# VGA.net
KiCad netlist of a schematic drawn in Altium Designer
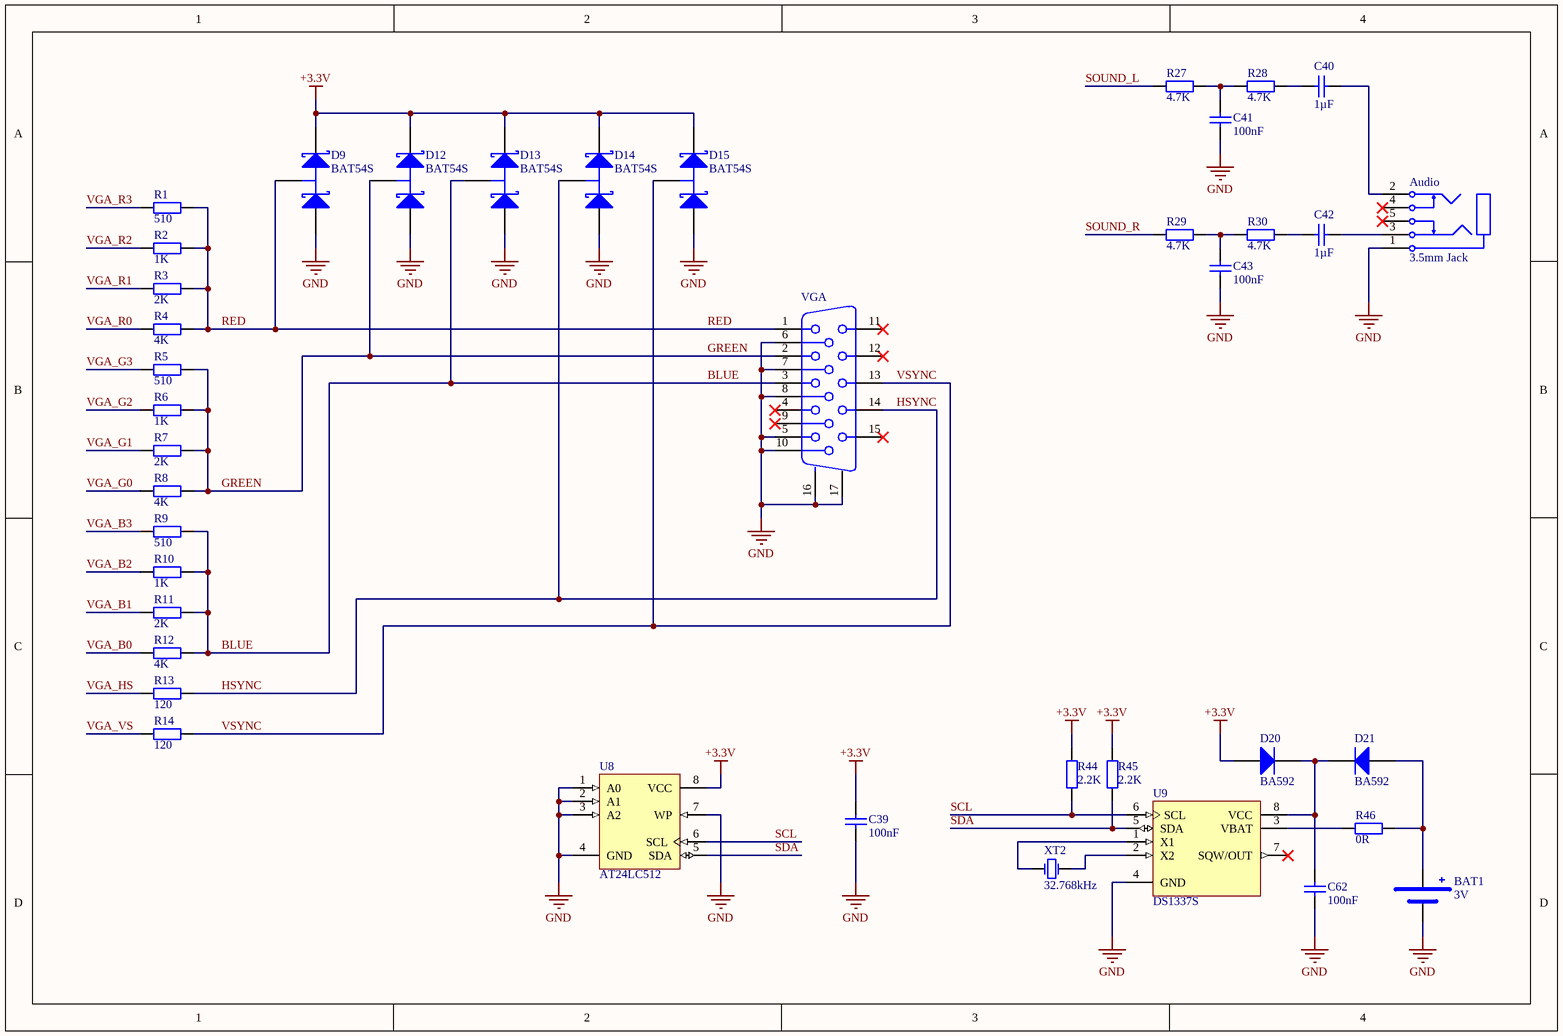
[diagram p0: VGA.SchDoc]

(export (version "E")
  (design (tool "Eeschema 10.0.6"))
  (components
    (comp (ref "Audio")
      (value "3.5mm Jack")
      (footprint "SJ1-353XNG")
      (libsource (lib "eon_lib") (part "Phono Jack"))
    )
    (comp (ref "BAT1")
      (value "3V")
      (footprint "CR2032 HOLDER - Vertical")
      (libsource (lib "eon_lib") (part "CR2032 Battery"))
    )
    (comp (ref "C39")
      (value "100nF")
      (footprint "RESC2012N")
      (description "Capacitor")
      (fields (field (name "PUBLISHER") "Altium Limited"))
      (libsource (lib "eon_lib") (part "Capacitor"))
    )
    (comp (ref "C40")
      (value "1µF")
      (footprint "6-0805_n")
      (description "Capacitor")
      (fields (field (name "Comment") "Cap") (field (name "PUBLISHER") "Altium Limited"))
      (libsource (lib "Miscellaneous Devices") (part "Cap"))
    )
    (comp (ref "C41")
      (value "100nF")
      (footprint "6-0805_n")
      (description "Capacitor")
      (fields (field (name "Comment") "Cap") (field (name "PUBLISHER") "Altium Limited"))
      (libsource (lib "Miscellaneous Devices") (part "Cap"))
    )
    (comp (ref "C42")
      (value "1µF")
      (footprint "6-0805_n")
      (description "Capacitor")
      (fields (field (name "Comment") "Cap") (field (name "PUBLISHER") "Altium Limited"))
      (libsource (lib "Miscellaneous Devices") (part "Cap"))
    )
    (comp (ref "C43")
      (value "100nF")
      (footprint "6-0805_n")
      (description "Capacitor")
      (fields (field (name "Comment") "Cap") (field (name "PUBLISHER") "Altium Limited"))
      (libsource (lib "Miscellaneous Devices") (part "Cap"))
    )
    (comp (ref "C62")
      (value "100nF")
      (footprint "RESC2012N")
      (description "Capacitor")
      (fields (field (name "PUBLISHER") "Altium Limited"))
      (libsource (lib "eon_lib") (part "Capacitor"))
    )
    (comp (ref "D9")
      (value "BAT54S")
      (footprint "SOT23_N")
      (description "Schottky Barrier Double Diode")
      (fields (field (name "PUBLISHER") "Altium Limited"))
      (libsource (lib "Philips Discrete Diode - Schottky") (part "BAT54S"))
    )
    (comp (ref "D12")
      (value "BAT54S")
      (footprint "SOT23_N")
      (description "Schottky Barrier Double Diode")
      (fields (field (name "PUBLISHER") "Altium Limited"))
      (libsource (lib "Philips Discrete Diode - Schottky") (part "BAT54S"))
    )
    (comp (ref "D13")
      (value "BAT54S")
      (footprint "SOT23_N")
      (description "Schottky Barrier Double Diode")
      (fields (field (name "PUBLISHER") "Altium Limited"))
      (libsource (lib "Philips Discrete Diode - Schottky") (part "BAT54S"))
    )
    (comp (ref "D14")
      (value "BAT54S")
      (footprint "SOT23_N")
      (description "Schottky Barrier Double Diode")
      (fields (field (name "PUBLISHER") "Altium Limited"))
      (libsource (lib "Philips Discrete Diode - Schottky") (part "BAT54S"))
    )
    (comp (ref "D15")
      (value "BAT54S")
      (footprint "SOT23_N")
      (description "Schottky Barrier Double Diode")
      (fields (field (name "PUBLISHER") "Altium Limited"))
      (libsource (lib "Philips Discrete Diode - Schottky") (part "BAT54S"))
    )
    (comp (ref "D20")
      (value "BA592")
      (footprint "SOD-323")
      (description "Silicon RF Switching Diode for VHF Band Switching in TV/VTR Tuners")
      (fields (field (name "PUBLISHER") "Altium Limited"))
      (libsource (lib "Infineon Discrete Diode") (part "BA592"))
    )
    (comp (ref "D21")
      (value "BA592")
      (footprint "SOD-323")
      (description "Silicon RF Switching Diode for VHF Band Switching in TV/VTR Tuners")
      (fields (field (name "PUBLISHER") "Altium Limited"))
      (libsource (lib "Infineon Discrete Diode") (part "BA592"))
    )
    (comp (ref "R1")
      (value "510")
      (footprint "6-0805_N")
      (description "Resistor")
      (fields (field (name "Comment") "Res2") (field (name "PUBLISHER") "Altium Limited"))
      (libsource (lib "Miscellaneous Devices") (part "Res2"))
    )
    (comp (ref "R2")
      (value "1K")
      (footprint "6-0805_N")
      (description "Resistor")
      (fields (field (name "Comment") "Res2") (field (name "PUBLISHER") "Altium Limited"))
      (libsource (lib "Miscellaneous Devices") (part "Res2"))
    )
    (comp (ref "R3")
      (value "2K")
      (footprint "6-0805_N")
      (description "Resistor")
      (fields (field (name "Comment") "Res2") (field (name "PUBLISHER") "Altium Limited"))
      (libsource (lib "Miscellaneous Devices") (part "Res2"))
    )
    (comp (ref "R4")
      (value "4K")
      (footprint "6-0805_N")
      (description "Resistor")
      (fields (field (name "Comment") "Res2") (field (name "PUBLISHER") "Altium Limited"))
      (libsource (lib "Miscellaneous Devices") (part "Res2"))
    )
    (comp (ref "R5")
      (value "510")
      (footprint "6-0805_N")
      (description "Resistor")
      (fields (field (name "Comment") "Res2") (field (name "PUBLISHER") "Altium Limited"))
      (libsource (lib "Miscellaneous Devices") (part "Res2"))
    )
    (comp (ref "R6")
      (value "1K")
      (footprint "6-0805_N")
      (description "Resistor")
      (fields (field (name "Comment") "Res2") (field (name "PUBLISHER") "Altium Limited"))
      (libsource (lib "Miscellaneous Devices") (part "Res2"))
    )
    (comp (ref "R7")
      (value "2K")
      (footprint "6-0805_N")
      (description "Resistor")
      (fields (field (name "Comment") "Res2") (field (name "PUBLISHER") "Altium Limited"))
      (libsource (lib "Miscellaneous Devices") (part "Res2"))
    )
    (comp (ref "R8")
      (value "4K")
      (footprint "6-0805_N")
      (description "Resistor")
      (fields (field (name "Comment") "Res2") (field (name "PUBLISHER") "Altium Limited"))
      (libsource (lib "Miscellaneous Devices") (part "Res2"))
    )
    (comp (ref "R9")
      (value "510")
      (footprint "6-0805_N")
      (description "Resistor")
      (fields (field (name "Comment") "Res2") (field (name "PUBLISHER") "Altium Limited"))
      (libsource (lib "Miscellaneous Devices") (part "Res2"))
    )
    (comp (ref "R10")
      (value "1K")
      (footprint "6-0805_N")
      (description "Resistor")
      (fields (field (name "Comment") "Res2") (field (name "PUBLISHER") "Altium Limited"))
      (libsource (lib "Miscellaneous Devices") (part "Res2"))
    )
    (comp (ref "R11")
      (value "2K")
      (footprint "6-0805_N")
      (description "Resistor")
      (fields (field (name "Comment") "Res2") (field (name "PUBLISHER") "Altium Limited"))
      (libsource (lib "Miscellaneous Devices") (part "Res2"))
    )
    (comp (ref "R12")
      (value "4K")
      (footprint "6-0805_N")
      (description "Resistor")
      (fields (field (name "Comment") "Res2") (field (name "PUBLISHER") "Altium Limited"))
      (libsource (lib "Miscellaneous Devices") (part "Res2"))
    )
    (comp (ref "R13")
      (value "120")
      (footprint "6-0805_N")
      (description "Resistor")
      (fields (field (name "Comment") "Res2") (field (name "PUBLISHER") "Altium Limited"))
      (libsource (lib "Miscellaneous Devices") (part "Res2"))
    )
    (comp (ref "R14")
      (value "120")
      (footprint "6-0805_N")
      (description "Resistor")
      (fields (field (name "Comment") "Res2") (field (name "PUBLISHER") "Altium Limited"))
      (libsource (lib "Miscellaneous Devices") (part "Res2"))
    )
    (comp (ref "R27")
      (value "4.7K")
      (footprint "6-0805_N")
      (description "Resistor")
      (fields (field (name "Comment") "Res2") (field (name "PUBLISHER") "Altium Limited"))
      (libsource (lib "") (part "Res2_1"))
    )
    (comp (ref "R28")
      (value "4.7K")
      (footprint "6-0805_N")
      (description "Resistor")
      (fields (field (name "Comment") "Res2") (field (name "PUBLISHER") "Altium Limited"))
      (libsource (lib "") (part "Res2_1"))
    )
    (comp (ref "R29")
      (value "4.7K")
      (footprint "6-0805_N")
      (description "Resistor")
      (fields (field (name "Comment") "Res2") (field (name "PUBLISHER") "Altium Limited"))
      (libsource (lib "") (part "Res2_1"))
    )
    (comp (ref "R30")
      (value "4.7K")
      (footprint "6-0805_N")
      (description "Resistor")
      (fields (field (name "Comment") "Res2") (field (name "PUBLISHER") "Altium Limited"))
      (libsource (lib "Miscellaneous Devices") (part "Res2"))
    )
    (comp (ref "R44")
      (value "2.2K")
      (footprint "RESC2012N")
      (description "Resistor")
      (fields (field (name "PUBLISHER") "Altium Limited"))
      (libsource (lib "eon_lib") (part "Resistor"))
    )
    (comp (ref "R45")
      (value "2.2K")
      (footprint "RESC2012N")
      (description "Resistor")
      (fields (field (name "PUBLISHER") "Altium Limited"))
      (libsource (lib "eon_lib") (part "Resistor"))
    )
    (comp (ref "R46")
      (value "0R")
      (footprint "RESC2012N")
      (description "Resistor")
      (fields (field (name "PUBLISHER") "Altium Limited"))
      (libsource (lib "") (part "Resistor_1"))
    )
    (comp (ref "U8")
      (value "AT24LC512")
      (footprint "8S1_N")
      (description "1Kbit (128 x 8), 2-wire Bus Automotive Serial EEPROM with Write Protect, 2.5V, 8-Pin SOIC, Bulk")
      (fields (field (name "PUBLISHER") "Altium Limited"))
      (libsource (lib "Atmel Memory Serial EEPROM") (part "AT24C01BN-SP25-B"))
    )
    (comp (ref "U9")
      (value "DS1337S")
      (footprint "SOIC8N_N")
      (description "64 X 8 Serial Real-Time Clock")
      (fields (field (name "PUBLISHER") "Altium Limited"))
      (libsource (lib "Dallas Peripheral Real Time Clock") (part "DS1307Z"))
    )
    (comp (ref "VGA")
      (value "Video")
      (footprint "VGA Connector")
      (libsource (lib "Connectors") (part "VGA Connector"))
    )
    (comp (ref "XT2")
      (value "32.768kHz")
      (footprint "SMD Clock Quarz")
      (fields (field (name "Comment") "XTAL"))
      (libsource (lib "eon_lib") (part "XTAL"))
    )
  )
  (nets
    (net (code "1") (name "+3.3V") (class "Default")
      (node (ref "C39") (pin "1") (pinfunction "1_1") (pintype "passive"))
      (node (ref "D12") (pin "2") (pinfunction "K_2") (pintype "passive"))
      (node (ref "D13") (pin "2") (pinfunction "K_2") (pintype "passive"))
      (node (ref "D14") (pin "2") (pinfunction "K_2") (pintype "passive"))
      (node (ref "D15") (pin "2") (pinfunction "K_2") (pintype "passive"))
      (node (ref "D20") (pin "2") (pinfunction "A_2") (pintype "passive"))
      (node (ref "D9") (pin "2") (pinfunction "K_2") (pintype "passive"))
      (node (ref "R44") (pin "2") (pinfunction "2_2") (pintype "passive"))
      (node (ref "R45") (pin "2") (pinfunction "2_2") (pintype "passive"))
      (node (ref "U8") (pin "8") (pinfunction "VCC_8") (pintype "power_in"))
    )
    (net (code "2") (name "/BLUE") (class "Default")
      (node (ref "D13") (pin "3") (pinfunction "C_3") (pintype "passive"))
      (node (ref "R10") (pin "1") (pinfunction "1_1") (pintype "passive"))
      (node (ref "R11") (pin "1") (pinfunction "1_1") (pintype "passive"))
      (node (ref "R12") (pin "1") (pinfunction "1_1") (pintype "passive"))
      (node (ref "R9") (pin "1") (pinfunction "1_1") (pintype "passive"))
      (node (ref "VGA") (pin "3") (pinfunction "3_3") (pintype "passive"))
    )
    (net (code "3") (name "/GREEN") (class "Default")
      (node (ref "D12") (pin "3") (pinfunction "C_3") (pintype "passive"))
      (node (ref "R5") (pin "1") (pinfunction "1_1") (pintype "passive"))
      (node (ref "R6") (pin "1") (pinfunction "1_1") (pintype "passive"))
      (node (ref "R7") (pin "1") (pinfunction "1_1") (pintype "passive"))
      (node (ref "R8") (pin "1") (pinfunction "1_1") (pintype "passive"))
      (node (ref "VGA") (pin "2") (pinfunction "2_2") (pintype "passive"))
    )
    (net (code "4") (name "/HSYNC") (class "Default")
      (node (ref "D14") (pin "3") (pinfunction "C_3") (pintype "passive"))
      (node (ref "R13") (pin "1") (pinfunction "1_1") (pintype "passive"))
      (node (ref "VGA") (pin "14") (pinfunction "14_14") (pintype "passive"))
    )
    (net (code "5") (name "/RED") (class "Default")
      (node (ref "D9") (pin "3") (pinfunction "C_3") (pintype "passive"))
      (node (ref "R1") (pin "1") (pinfunction "1_1") (pintype "passive"))
      (node (ref "R2") (pin "1") (pinfunction "1_1") (pintype "passive"))
      (node (ref "R3") (pin "1") (pinfunction "1_1") (pintype "passive"))
      (node (ref "R4") (pin "1") (pinfunction "1_1") (pintype "passive"))
      (node (ref "VGA") (pin "1") (pinfunction "1_1") (pintype "passive"))
    )
    (net (code "6") (name "/SCL") (class "Default")
      (node (ref "R44") (pin "1") (pinfunction "1_1") (pintype "passive"))
      (node (ref "U8") (pin "6") (pinfunction "SCL_6") (pintype "input"))
      (node (ref "U9") (pin "6") (pinfunction "SCL_6") (pintype "input"))
    )
    (net (code "7") (name "/SDA") (class "Default")
      (node (ref "R45") (pin "1") (pinfunction "1_1") (pintype "passive"))
      (node (ref "U8") (pin "5") (pinfunction "SDA_5") (pintype "bidirectional"))
      (node (ref "U9") (pin "5") (pinfunction "SDA_5") (pintype "bidirectional"))
    )
    (net (code "8") (name "/SOUND_L") (class "Default")
      (node (ref "R27") (pin "1") (pinfunction "1_1") (pintype "passive"))
    )
    (net (code "9") (name "/SOUND_R") (class "Default")
      (node (ref "R29") (pin "1") (pinfunction "1_1") (pintype "passive"))
    )
    (net (code "10") (name "/VGA_B0") (class "Default")
      (node (ref "R12") (pin "2") (pinfunction "2_2") (pintype "passive"))
    )
    (net (code "11") (name "/VGA_B1") (class "Default")
      (node (ref "R11") (pin "2") (pinfunction "2_2") (pintype "passive"))
    )
    (net (code "12") (name "/VGA_B2") (class "Default")
      (node (ref "R10") (pin "2") (pinfunction "2_2") (pintype "passive"))
    )
    (net (code "13") (name "/VGA_B3") (class "Default")
      (node (ref "R9") (pin "2") (pinfunction "2_2") (pintype "passive"))
    )
    (net (code "14") (name "/VGA_G0") (class "Default")
      (node (ref "R8") (pin "2") (pinfunction "2_2") (pintype "passive"))
    )
    (net (code "15") (name "/VGA_G1") (class "Default")
      (node (ref "R7") (pin "2") (pinfunction "2_2") (pintype "passive"))
    )
    (net (code "16") (name "/VGA_G2") (class "Default")
      (node (ref "R6") (pin "2") (pinfunction "2_2") (pintype "passive"))
    )
    (net (code "17") (name "/VGA_G3") (class "Default")
      (node (ref "R5") (pin "2") (pinfunction "2_2") (pintype "passive"))
    )
    (net (code "18") (name "/VGA_HS") (class "Default")
      (node (ref "R13") (pin "2") (pinfunction "2_2") (pintype "passive"))
    )
    (net (code "19") (name "/VGA_R0") (class "Default")
      (node (ref "R4") (pin "2") (pinfunction "2_2") (pintype "passive"))
    )
    (net (code "20") (name "/VGA_R1") (class "Default")
      (node (ref "R3") (pin "2") (pinfunction "2_2") (pintype "passive"))
    )
    (net (code "21") (name "/VGA_R2") (class "Default")
      (node (ref "R2") (pin "2") (pinfunction "2_2") (pintype "passive"))
    )
    (net (code "22") (name "/VGA_R3") (class "Default")
      (node (ref "R1") (pin "2") (pinfunction "2_2") (pintype "passive"))
    )
    (net (code "23") (name "/VGA_VS") (class "Default")
      (node (ref "R14") (pin "2") (pinfunction "2_2") (pintype "passive"))
    )
    (net (code "24") (name "/VSYNC") (class "Default")
      (node (ref "D15") (pin "3") (pinfunction "C_3") (pintype "passive"))
      (node (ref "R14") (pin "1") (pinfunction "1_1") (pintype "passive"))
      (node (ref "VGA") (pin "13") (pinfunction "13_13") (pintype "passive"))
    )
    (net (code "25") (name "GND") (class "Default")
      (node (ref "Audio") (pin "1") (pinfunction "1_1") (pintype "passive"))
      (node (ref "BAT1") (pin "2") (pinfunction "2_2") (pintype "passive"))
      (node (ref "C39") (pin "2") (pinfunction "2_2") (pintype "passive"))
      (node (ref "C41") (pin "1") (pinfunction "1_1") (pintype "passive"))
      (node (ref "C43") (pin "1") (pinfunction "1_1") (pintype "passive"))
      (node (ref "C62") (pin "2") (pinfunction "2_2") (pintype "passive"))
      (node (ref "D12") (pin "1") (pinfunction "A_1") (pintype "passive"))
      (node (ref "D13") (pin "1") (pinfunction "A_1") (pintype "passive"))
      (node (ref "D14") (pin "1") (pinfunction "A_1") (pintype "passive"))
      (node (ref "D15") (pin "1") (pinfunction "A_1") (pintype "passive"))
      (node (ref "D9") (pin "1") (pinfunction "A_1") (pintype "passive"))
      (node (ref "U8") (pin "1") (pinfunction "A0_1") (pintype "input"))
      (node (ref "U8") (pin "2") (pinfunction "A1_2") (pintype "input"))
      (node (ref "U8") (pin "3") (pinfunction "A2_3") (pintype "input"))
      (node (ref "U8") (pin "4") (pinfunction "GND_4") (pintype "power_in"))
      (node (ref "U8") (pin "7") (pinfunction "WP_7") (pintype "input"))
      (node (ref "U9") (pin "4") (pinfunction "GND_4") (pintype "power_in"))
      (node (ref "VGA") (pin "10") (pinfunction "10_10") (pintype "power_in"))
      (node (ref "VGA") (pin "16") (pinfunction "MH1_16") (pintype "passive"))
      (node (ref "VGA") (pin "17") (pinfunction "MH2_17") (pintype "passive"))
      (node (ref "VGA") (pin "5") (pinfunction "5_5") (pintype "power_in"))
      (node (ref "VGA") (pin "6") (pinfunction "6_6") (pintype "power_in"))
      (node (ref "VGA") (pin "7") (pinfunction "7_7") (pintype "power_in"))
      (node (ref "VGA") (pin "8") (pinfunction "8_8") (pintype "power_in"))
    )
    (net (code "26") (name "Net-(Audio-Pad2)") (class "Default")
      (node (ref "Audio") (pin "2") (pinfunction "2_2") (pintype "passive"))
      (node (ref "C40") (pin "1") (pinfunction "1_1") (pintype "passive"))
    )
    (net (code "27") (name "Net-(Audio-Pad3)") (class "Default")
      (node (ref "Audio") (pin "3") (pinfunction "3_3") (pintype "passive"))
      (node (ref "C42") (pin "1") (pinfunction "1_1") (pintype "passive"))
    )
    (net (code "28") (name "Net-(C40-Pad2)") (class "Default")
      (node (ref "C40") (pin "2") (pinfunction "2_2") (pintype "passive"))
      (node (ref "R28") (pin "2") (pinfunction "2_2") (pintype "passive"))
    )
    (net (code "29") (name "Net-(C41-Pad2)") (class "Default")
      (node (ref "C41") (pin "2") (pinfunction "2_2") (pintype "passive"))
      (node (ref "R27") (pin "2") (pinfunction "2_2") (pintype "passive"))
      (node (ref "R28") (pin "1") (pinfunction "1_1") (pintype "passive"))
    )
    (net (code "30") (name "Net-(C42-Pad2)") (class "Default")
      (node (ref "C42") (pin "2") (pinfunction "2_2") (pintype "passive"))
      (node (ref "R30") (pin "1") (pinfunction "1_1") (pintype "passive"))
    )
    (net (code "31") (name "Net-(C43-Pad2)") (class "Default")
      (node (ref "C43") (pin "2") (pinfunction "2_2") (pintype "passive"))
      (node (ref "R29") (pin "2") (pinfunction "2_2") (pintype "passive"))
      (node (ref "R30") (pin "2") (pinfunction "2_2") (pintype "passive"))
    )
    (net (code "32") (name "Net-(D20-K)") (class "Default")
      (node (ref "C62") (pin "1") (pinfunction "1_1") (pintype "passive"))
      (node (ref "D20") (pin "1") (pinfunction "K_1") (pintype "passive"))
      (node (ref "D21") (pin "1") (pinfunction "K_1") (pintype "passive"))
      (node (ref "U9") (pin "8") (pinfunction "VCC_8") (pintype "power_in"))
    )
    (net (code "33") (name "Net-(D21-A)") (class "Default")
      (node (ref "BAT1") (pin "1") (pinfunction "1_1") (pintype "passive"))
      (node (ref "D21") (pin "2") (pinfunction "A_2") (pintype "passive"))
      (node (ref "R46") (pin "1") (pinfunction "1_1") (pintype "passive"))
    )
    (net (code "34") (name "Net-(U9-VBAT)") (class "Default")
      (node (ref "R46") (pin "2") (pinfunction "2_2") (pintype "passive"))
      (node (ref "U9") (pin "3") (pinfunction "VBAT_3") (pintype "power_in"))
    )
    (net (code "35") (name "Net-(U9-X1)") (class "Default")
      (node (ref "U9") (pin "1") (pinfunction "X1_1") (pintype "input"))
      (node (ref "XT2") (pin "1") (pinfunction "OSC1_1") (pintype "passive"))
    )
    (net (code "36") (name "Net-(U9-X2)") (class "Default")
      (node (ref "U9") (pin "2") (pinfunction "X2_2") (pintype "input"))
      (node (ref "XT2") (pin "2") (pinfunction "OSC2_2") (pintype "passive"))
    )
    (net (code "37") (name "unconnected-(Audio-Pad4)") (class "Default")
      (node (ref "Audio") (pin "4") (pinfunction "4_4") (pintype "passive+no_connect"))
    )
    (net (code "38") (name "unconnected-(Audio-Pad5)") (class "Default")
      (node (ref "Audio") (pin "5") (pinfunction "5_5") (pintype "passive+no_connect"))
    )
    (net (code "39") (name "unconnected-(U9-SQW{slash}OUT-Pad7)") (class "Default")
      (node (ref "U9") (pin "7") (pinfunction "SQW/OUT_7") (pintype "output+no_connect"))
    )
    (net (code "40") (name "unconnected-(VGA-Pad4)") (class "Default")
      (node (ref "VGA") (pin "4") (pinfunction "4_4") (pintype "passive+no_connect"))
    )
    (net (code "41") (name "unconnected-(VGA-Pad9)") (class "Default")
      (node (ref "VGA") (pin "9") (pinfunction "9_9") (pintype "passive+no_connect"))
    )
    (net (code "42") (name "unconnected-(VGA-Pad11)") (class "Default")
      (node (ref "VGA") (pin "11") (pinfunction "11_11") (pintype "power_in+no_connect"))
    )
    (net (code "43") (name "unconnected-(VGA-Pad12)") (class "Default")
      (node (ref "VGA") (pin "12") (pinfunction "12_12") (pintype "passive+no_connect"))
    )
    (net (code "44") (name "unconnected-(VGA-Pad15)") (class "Default")
      (node (ref "VGA") (pin "15") (pinfunction "15_15") (pintype "passive+no_connect"))
    )
  )
)
